# MainSCH.net
KiCad netlist of a schematic drawn in Altium Designer
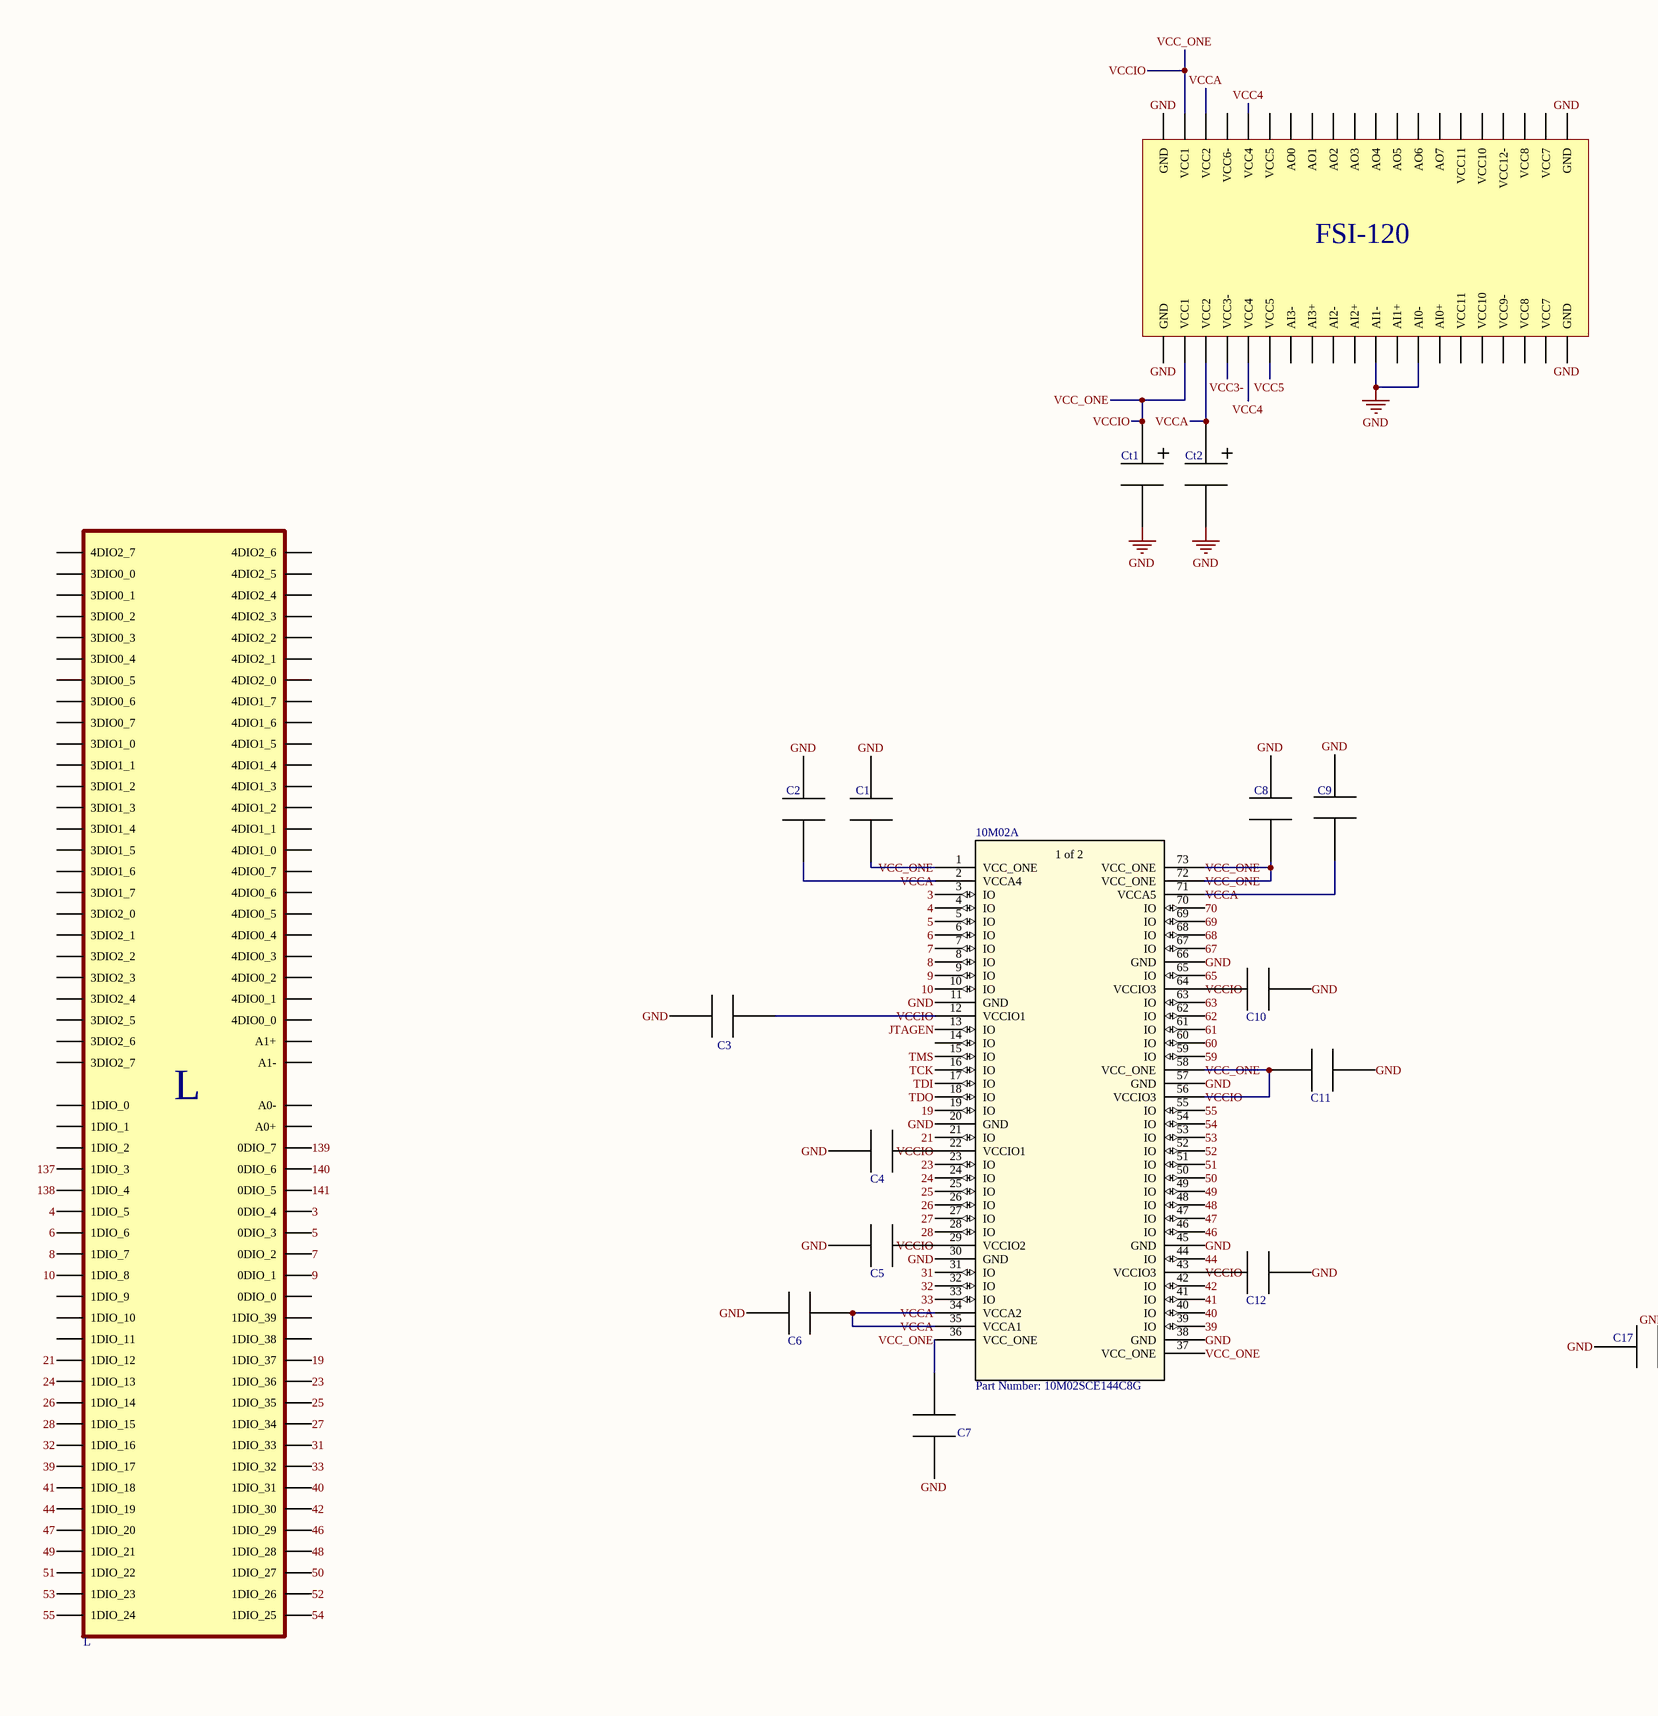
[diagram p0: MainSCH.SchDoc, left]
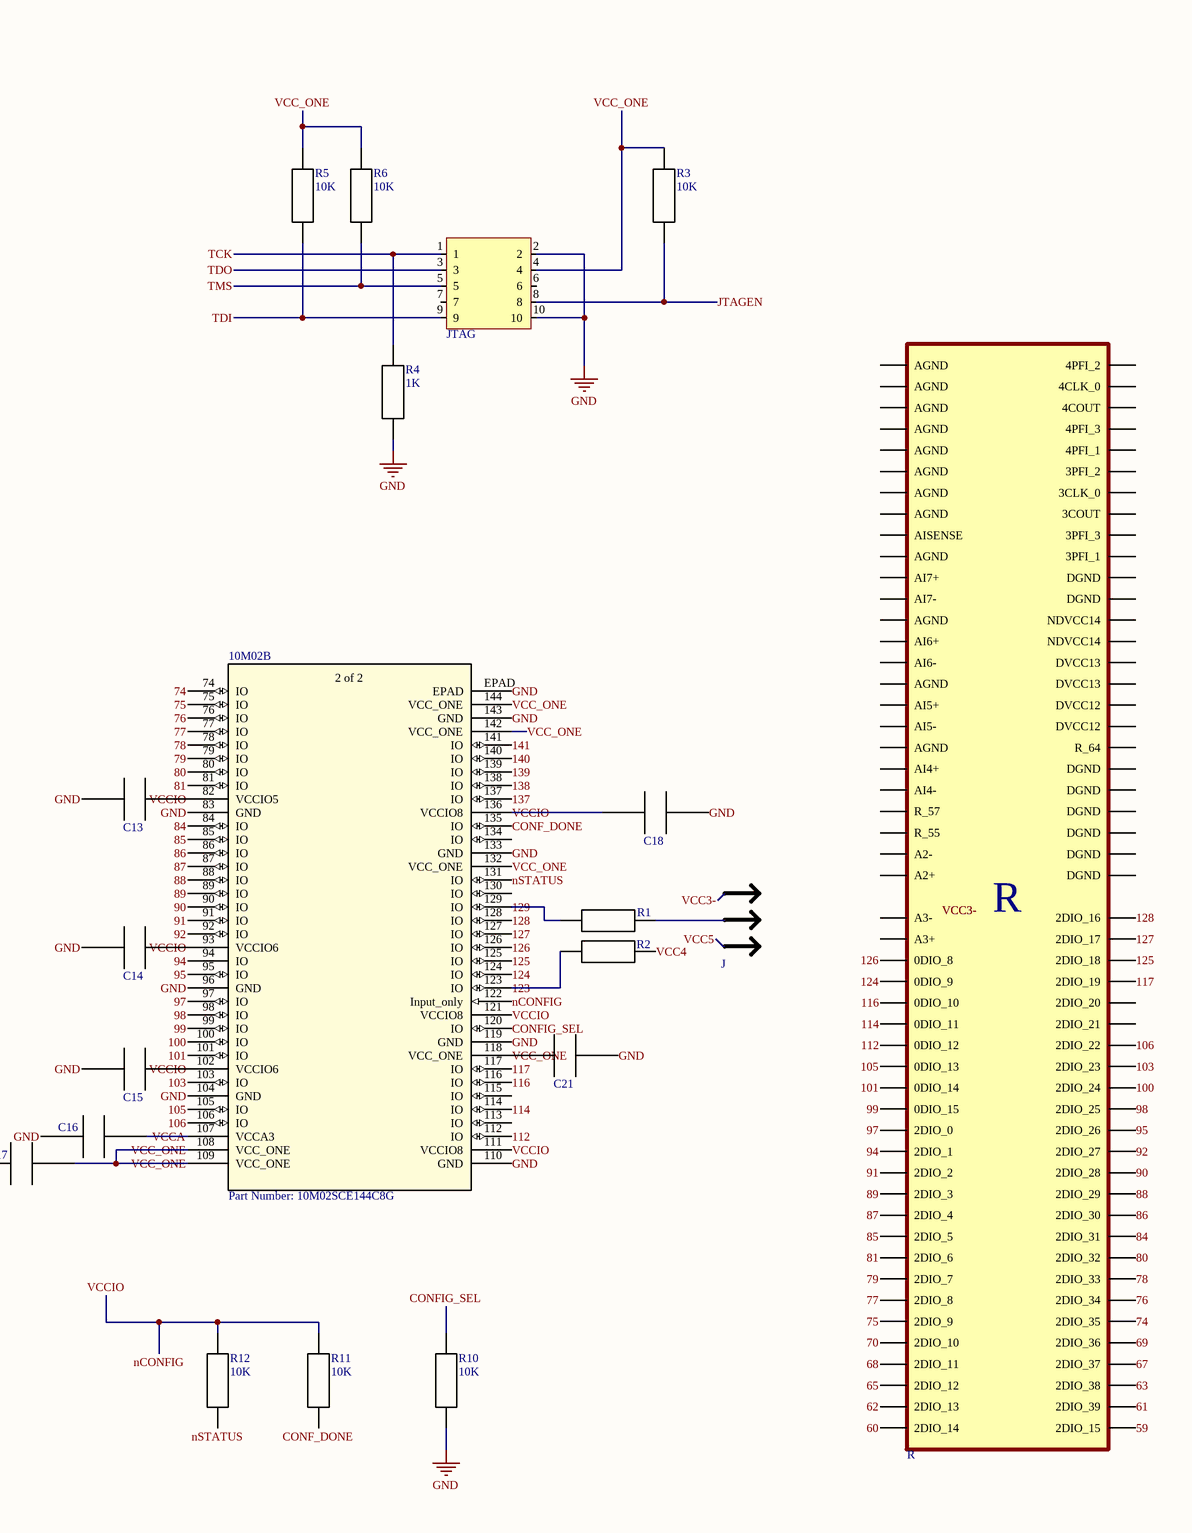
[diagram p1: MainSCH.SchDoc, right]

(export (version "E")
  (design (tool "Eeschema 10.0.6"))
  (components
    (comp (ref "*") (value "JTAG") (footprint "JTAG") (libsource (lib "2020-02-13_08-55-10") (part "JTAG")))
    (comp (ref "10M02")
      (value "Part Number: 10M02SCE144C8G")
      (footprint "EQFP-144_A:1P65_")
      (description "No Description Available")
      (fields
        (field (name "MANUFACTURER_PART_NUMBER") "10M02SCE144C8G")
        (field (name "COPYRIGHT") "Copyright (C) 2018 Accelerated Designs. All rights reserved")
      )
      (libsource (lib "2020-02-13_08-55-10") (part "10M02SCE144C8G"))
    )
    (comp (ref "C1")
      (value "*")
      (footprint "0805")
      (description "0805 ceramic capacitor")
      (libsource (lib "test_lib") (part "C0805"))
    )
    (comp (ref "C2")
      (value "*")
      (footprint "0805")
      (description "0805 ceramic capacitor")
      (libsource (lib "test_lib") (part "C0805"))
    )
    (comp (ref "C3")
      (value "*")
      (footprint "0805")
      (description "0805 ceramic capacitor")
      (libsource (lib "test_lib") (part "C0805"))
    )
    (comp (ref "C4")
      (value "*")
      (footprint "0805")
      (description "0805 ceramic capacitor")
      (libsource (lib "test_lib") (part "C0805"))
    )
    (comp (ref "C5")
      (value "*")
      (footprint "0805")
      (description "0805 ceramic capacitor")
      (libsource (lib "test_lib") (part "C0805"))
    )
    (comp (ref "C6")
      (value "*")
      (footprint "0805")
      (description "0805 ceramic capacitor")
      (libsource (lib "test_lib") (part "C0805"))
    )
    (comp (ref "C7")
      (value "*")
      (footprint "0805")
      (description "0805 ceramic capacitor")
      (libsource (lib "test_lib") (part "C0805"))
    )
    (comp (ref "C8")
      (value "*")
      (footprint "0805")
      (description "0805 ceramic capacitor")
      (libsource (lib "test_lib") (part "C0805"))
    )
    (comp (ref "C9")
      (value "*")
      (footprint "0805")
      (description "0805 ceramic capacitor")
      (libsource (lib "test_lib") (part "C0805"))
    )
    (comp (ref "C10")
      (value "*")
      (footprint "0805")
      (description "0805 ceramic capacitor")
      (libsource (lib "test_lib") (part "C0805"))
    )
    (comp (ref "C11")
      (value "*")
      (footprint "0805")
      (description "0805 ceramic capacitor")
      (libsource (lib "test_lib") (part "C0805"))
    )
    (comp (ref "C12")
      (value "*")
      (footprint "0805")
      (description "0805 ceramic capacitor")
      (libsource (lib "test_lib") (part "C0805"))
    )
    (comp (ref "C13")
      (value "*")
      (footprint "0805")
      (description "0805 ceramic capacitor")
      (libsource (lib "test_lib") (part "C0805"))
    )
    (comp (ref "C14")
      (value "*")
      (footprint "0805")
      (description "0805 ceramic capacitor")
      (libsource (lib "test_lib") (part "C0805"))
    )
    (comp (ref "C15")
      (value "*")
      (footprint "0805")
      (description "0805 ceramic capacitor")
      (libsource (lib "test_lib") (part "C0805"))
    )
    (comp (ref "C16")
      (value "*")
      (footprint "0805")
      (description "0805 ceramic capacitor")
      (libsource (lib "test_lib") (part "C0805"))
    )
    (comp (ref "C17")
      (value "*")
      (footprint "0805")
      (description "0805 ceramic capacitor")
      (libsource (lib "test_lib") (part "C0805"))
    )
    (comp (ref "C18")
      (value "*")
      (footprint "0805")
      (description "0805 ceramic capacitor")
      (libsource (lib "test_lib") (part "C0805"))
    )
    (comp (ref "C21")
      (value "*")
      (footprint "0805")
      (description "0805 ceramic capacitor")
      (libsource (lib "test_lib") (part "C0805"))
    )
    (comp (ref "Ct1")
      (value "C_Ta")
      (footprint "C_Ta")
      (description "tantalum capacitor")
      (libsource (lib "test_lib") (part "C_Ta"))
    )
    (comp (ref "Ct2")
      (value "C_Ta")
      (footprint "C_Ta")
      (description "tantalum capacitor")
      (libsource (lib "test_lib") (part "C_Ta"))
    )
    (comp (ref "J")
      (value "JUMPER_SWITCH_2S")
      (footprint "JUMPER_SWITCH_2S")
      (description "2 state jumper switch")
      (libsource (lib "test_lib") (part "JUMPER_SWITCH_2S"))
    )
    (comp (ref "L")
      (value "FSI-150-L")
      (footprint "FSI-150")
      (description "fsi 150 left")
      (libsource (lib "test_lib") (part "FSI-150-L"))
    )
    (comp (ref "R")
      (value "FSI-150-R")
      (footprint "FSI-150")
      (description "fsi 150 right")
      (libsource (lib "test_lib") (part "FSI-150-R"))
    )
    (comp (ref "R1")
      (value "*")
      (footprint "0805")
      (description "0805 resistor")
      (libsource (lib "test_lib") (part "R0805"))
    )
    (comp (ref "R2")
      (value "*")
      (footprint "0805")
      (description "0805 resistor")
      (libsource (lib "test_lib") (part "R0805"))
    )
    (comp (ref "R3")
      (value "10K")
      (footprint "0805")
      (description "0805 resistor")
      (libsource (lib "test_lib") (part "R0805"))
    )
    (comp (ref "R4")
      (value "1K")
      (footprint "0805")
      (description "0805 resistor")
      (libsource (lib "test_lib") (part "R0805"))
    )
    (comp (ref "R5")
      (value "10K")
      (footprint "0805")
      (description "0805 resistor")
      (libsource (lib "test_lib") (part "R0805"))
    )
    (comp (ref "R6")
      (value "10K")
      (footprint "0805")
      (description "0805 resistor")
      (libsource (lib "test_lib") (part "R0805"))
    )
    (comp (ref "R10")
      (value "10K")
      (footprint "0805")
      (description "0805 resistor")
      (libsource (lib "test_lib") (part "R0805"))
    )
    (comp (ref "R11")
      (value "10K")
      (footprint "0805")
      (description "0805 resistor")
      (libsource (lib "test_lib") (part "R0805"))
    )
    (comp (ref "R12")
      (value "10K")
      (footprint "0805")
      (description "0805 resistor")
      (libsource (lib "test_lib") (part "R0805"))
    )
    (comp (ref "X") (value "FSI120") (footprint "FSI-120") (libsource (lib "test_lib") (part "FSI120")))
  )
  (nets
    (net (code "1") (name "/3") (class "Default")
      (node (ref "10M02") (pin "3") (pinfunction "IO_3") (pintype "bidirectional"))
      (node (ref "L") (pin "R_40") (pinfunction "0DIO_4_R_40") (pintype "passive"))
    )
    (net (code "2") (name "/4") (class "Default")
      (node (ref "10M02") (pin "4") (pinfunction "IO_4") (pintype "bidirectional"))
      (node (ref "L") (pin "R_39") (pinfunction "1DIO_5_R_39") (pintype "passive"))
    )
    (net (code "3") (name "/5") (class "Default")
      (node (ref "10M02") (pin "5") (pinfunction "IO_5") (pintype "bidirectional"))
      (node (ref "L") (pin "R_38") (pinfunction "0DIO_3_R_38") (pintype "passive"))
    )
    (net (code "4") (name "/6") (class "Default")
      (node (ref "10M02") (pin "6") (pinfunction "IO_6") (pintype "bidirectional"))
      (node (ref "L") (pin "R_37") (pinfunction "1DIO_6_R_37") (pintype "passive"))
    )
    (net (code "5") (name "/7") (class "Default")
      (node (ref "10M02") (pin "7") (pinfunction "IO_7") (pintype "bidirectional"))
      (node (ref "L") (pin "R_36") (pinfunction "0DIO_2_R_36") (pintype "passive"))
    )
    (net (code "6") (name "/8") (class "Default")
      (node (ref "10M02") (pin "8") (pinfunction "IO_8") (pintype "bidirectional"))
      (node (ref "L") (pin "R_35") (pinfunction "1DIO_7_R_35") (pintype "passive"))
    )
    (net (code "7") (name "/9") (class "Default")
      (node (ref "10M02") (pin "9") (pinfunction "IO_9") (pintype "bidirectional"))
      (node (ref "L") (pin "R_34") (pinfunction "0DIO_1_R_34") (pintype "passive"))
    )
    (net (code "8") (name "/10") (class "Default")
      (node (ref "10M02") (pin "10") (pinfunction "IO_10") (pintype "bidirectional"))
      (node (ref "L") (pin "R_33") (pinfunction "1DIO_8_R_33") (pintype "passive"))
    )
    (net (code "9") (name "/19") (class "Default")
      (node (ref "10M02") (pin "19") (pinfunction "IO_19") (pintype "bidirectional"))
      (node (ref "L") (pin "R_26") (pinfunction "1DIO_37_R_26") (pintype "passive"))
    )
    (net (code "10") (name "/21") (class "Default")
      (node (ref "10M02") (pin "21") (pinfunction "IO_21") (pintype "bidirectional"))
      (node (ref "L") (pin "R_25") (pinfunction "1DIO_12_R_25") (pintype "passive"))
    )
    (net (code "11") (name "/23") (class "Default")
      (node (ref "10M02") (pin "23") (pinfunction "IO_23") (pintype "bidirectional"))
      (node (ref "L") (pin "R_24") (pinfunction "1DIO_36_R_24") (pintype "passive"))
    )
    (net (code "12") (name "/24") (class "Default")
      (node (ref "10M02") (pin "24") (pinfunction "IO_24") (pintype "bidirectional"))
      (node (ref "L") (pin "R_23") (pinfunction "1DIO_13_R_23") (pintype "passive"))
    )
    (net (code "13") (name "/25") (class "Default")
      (node (ref "10M02") (pin "25") (pinfunction "IO_25") (pintype "bidirectional"))
      (node (ref "L") (pin "R_22") (pinfunction "1DIO_35_R_22") (pintype "passive"))
    )
    (net (code "14") (name "/26") (class "Default")
      (node (ref "10M02") (pin "26") (pinfunction "IO_26") (pintype "bidirectional"))
      (node (ref "L") (pin "R_21") (pinfunction "1DIO_14_R_21") (pintype "passive"))
    )
    (net (code "15") (name "/27") (class "Default")
      (node (ref "10M02") (pin "27") (pinfunction "IO_27") (pintype "bidirectional"))
      (node (ref "L") (pin "R_20") (pinfunction "1DIO_34_R_20") (pintype "passive"))
    )
    (net (code "16") (name "/28") (class "Default")
      (node (ref "10M02") (pin "28") (pinfunction "IO_28") (pintype "bidirectional"))
      (node (ref "L") (pin "R_19") (pinfunction "1DIO_15_R_19") (pintype "passive"))
    )
    (net (code "17") (name "/31") (class "Default")
      (node (ref "10M02") (pin "31") (pinfunction "IO_31") (pintype "bidirectional"))
      (node (ref "L") (pin "R_18") (pinfunction "1DIO_33_R_18") (pintype "passive"))
    )
    (net (code "18") (name "/32") (class "Default")
      (node (ref "10M02") (pin "32") (pinfunction "IO_32") (pintype "bidirectional"))
      (node (ref "L") (pin "R_17") (pinfunction "1DIO_16_R_17") (pintype "passive"))
    )
    (net (code "19") (name "/33") (class "Default")
      (node (ref "10M02") (pin "33") (pinfunction "IO_33") (pintype "bidirectional"))
      (node (ref "L") (pin "R_16") (pinfunction "1DIO_32_R_16") (pintype "passive"))
    )
    (net (code "20") (name "/39") (class "Default")
      (node (ref "10M02") (pin "39") (pinfunction "IO_39") (pintype "bidirectional"))
      (node (ref "L") (pin "R_15") (pinfunction "1DIO_17_R_15") (pintype "passive"))
    )
    (net (code "21") (name "/40") (class "Default")
      (node (ref "10M02") (pin "40") (pinfunction "IO_40") (pintype "bidirectional"))
      (node (ref "L") (pin "R_14") (pinfunction "1DIO_31_R_14") (pintype "passive"))
    )
    (net (code "22") (name "/41") (class "Default")
      (node (ref "10M02") (pin "41") (pinfunction "IO_41") (pintype "bidirectional"))
      (node (ref "L") (pin "R_13") (pinfunction "1DIO_18_R_13") (pintype "passive"))
    )
    (net (code "23") (name "/42") (class "Default")
      (node (ref "10M02") (pin "42") (pinfunction "IO_42") (pintype "bidirectional"))
      (node (ref "L") (pin "R_12") (pinfunction "1DIO_30_R_12") (pintype "passive"))
    )
    (net (code "24") (name "/44") (class "Default")
      (node (ref "10M02") (pin "44") (pinfunction "IO_44") (pintype "bidirectional"))
      (node (ref "L") (pin "R_11") (pinfunction "1DIO_19_R_11") (pintype "passive"))
    )
    (net (code "25") (name "/46") (class "Default")
      (node (ref "10M02") (pin "46") (pinfunction "IO_46") (pintype "bidirectional"))
      (node (ref "L") (pin "R_10") (pinfunction "1DIO_29_R_10") (pintype "passive"))
    )
    (net (code "26") (name "/47") (class "Default")
      (node (ref "10M02") (pin "47") (pinfunction "IO_47") (pintype "bidirectional"))
      (node (ref "L") (pin "R_9") (pinfunction "1DIO_20_R_9") (pintype "passive"))
    )
    (net (code "27") (name "/48") (class "Default")
      (node (ref "10M02") (pin "48") (pinfunction "IO_48") (pintype "bidirectional"))
      (node (ref "L") (pin "R_8") (pinfunction "1DIO_28_R_8") (pintype "passive"))
    )
    (net (code "28") (name "/49") (class "Default")
      (node (ref "10M02") (pin "49") (pinfunction "IO_49") (pintype "bidirectional"))
      (node (ref "L") (pin "R_7") (pinfunction "1DIO_21_R_7") (pintype "passive"))
    )
    (net (code "29") (name "/50") (class "Default")
      (node (ref "10M02") (pin "50") (pinfunction "IO_50") (pintype "bidirectional"))
      (node (ref "L") (pin "R_6") (pinfunction "1DIO_27_R_6") (pintype "passive"))
    )
    (net (code "30") (name "/51") (class "Default")
      (node (ref "10M02") (pin "51") (pinfunction "IO_51") (pintype "bidirectional"))
      (node (ref "L") (pin "R_5") (pinfunction "1DIO_22_R_5") (pintype "passive"))
    )
    (net (code "31") (name "/52") (class "Default")
      (node (ref "10M02") (pin "52") (pinfunction "IO_52") (pintype "bidirectional"))
      (node (ref "L") (pin "R_4") (pinfunction "1DIO_26_R_4") (pintype "passive"))
    )
    (net (code "32") (name "/53") (class "Default")
      (node (ref "10M02") (pin "53") (pinfunction "IO_53") (pintype "bidirectional"))
      (node (ref "L") (pin "R_3") (pinfunction "1DIO_23_R_3") (pintype "passive"))
    )
    (net (code "33") (name "/54") (class "Default")
      (node (ref "10M02") (pin "54") (pinfunction "IO_54") (pintype "bidirectional"))
      (node (ref "L") (pin "R_2") (pinfunction "1DIO_25_R_2") (pintype "passive"))
    )
    (net (code "34") (name "/55") (class "Default")
      (node (ref "10M02") (pin "55") (pinfunction "IO_55") (pintype "bidirectional"))
      (node (ref "L") (pin "R_1") (pinfunction "1DIO_24_R_1") (pintype "passive"))
    )
    (net (code "35") (name "/59") (class "Default")
      (node (ref "10M02") (pin "59") (pinfunction "IO_59") (pintype "bidirectional"))
      (node (ref "R") (pin "R_2") (pinfunction "2DIO_15_R_2") (pintype "passive"))
    )
    (net (code "36") (name "/60") (class "Default")
      (node (ref "10M02") (pin "60") (pinfunction "IO_60") (pintype "bidirectional"))
      (node (ref "R") (pin "R_1") (pinfunction "2DIO_14_R_1") (pintype "passive"))
    )
    (net (code "37") (name "/61") (class "Default")
      (node (ref "10M02") (pin "61") (pinfunction "IO_61") (pintype "bidirectional"))
      (node (ref "R") (pin "R_4") (pinfunction "2DIO_39_R_4") (pintype "passive"))
    )
    (net (code "38") (name "/62") (class "Default")
      (node (ref "10M02") (pin "62") (pinfunction "IO_62") (pintype "bidirectional"))
      (node (ref "R") (pin "R_3") (pinfunction "2DIO_13_R_3") (pintype "passive"))
    )
    (net (code "39") (name "/63") (class "Default")
      (node (ref "10M02") (pin "63") (pinfunction "IO_63") (pintype "bidirectional"))
      (node (ref "R") (pin "R_6") (pinfunction "2DIO_38_R_6") (pintype "passive"))
    )
    (net (code "40") (name "/65") (class "Default")
      (node (ref "10M02") (pin "65") (pinfunction "IO_65") (pintype "bidirectional"))
      (node (ref "R") (pin "R_5") (pinfunction "2DIO_12_R_5") (pintype "passive"))
    )
    (net (code "41") (name "/67") (class "Default")
      (node (ref "10M02") (pin "67") (pinfunction "IO_67") (pintype "bidirectional"))
      (node (ref "R") (pin "R_8") (pinfunction "2DIO_37_R_8") (pintype "passive"))
    )
    (net (code "42") (name "/68") (class "Default")
      (node (ref "10M02") (pin "68") (pinfunction "IO_68") (pintype "bidirectional"))
      (node (ref "R") (pin "R_7") (pinfunction "2DIO_11_R_7") (pintype "passive"))
    )
    (net (code "43") (name "/69") (class "Default")
      (node (ref "10M02") (pin "69") (pinfunction "IO_69") (pintype "bidirectional"))
      (node (ref "R") (pin "R_10") (pinfunction "2DIO_36_R_10") (pintype "passive"))
    )
    (net (code "44") (name "/70") (class "Default")
      (node (ref "10M02") (pin "70") (pinfunction "IO_70") (pintype "bidirectional"))
      (node (ref "R") (pin "R_9") (pinfunction "2DIO_10_R_9") (pintype "passive"))
    )
    (net (code "45") (name "/74") (class "Default")
      (node (ref "10M02") (pin "74") (pinfunction "IO_74") (pintype "bidirectional"))
      (node (ref "R") (pin "R_12") (pinfunction "2DIO_35_R_12") (pintype "passive"))
    )
    (net (code "46") (name "/75") (class "Default")
      (node (ref "10M02") (pin "75") (pinfunction "IO_75") (pintype "bidirectional"))
      (node (ref "R") (pin "R_11") (pinfunction "2DIO_9_R_11") (pintype "passive"))
    )
    (net (code "47") (name "/76") (class "Default")
      (node (ref "10M02") (pin "76") (pinfunction "IO_76") (pintype "bidirectional"))
      (node (ref "R") (pin "R_14") (pinfunction "2DIO_34_R_14") (pintype "passive"))
    )
    (net (code "48") (name "/77") (class "Default")
      (node (ref "10M02") (pin "77") (pinfunction "IO_77") (pintype "bidirectional"))
      (node (ref "R") (pin "R_13") (pinfunction "2DIO_8_R_13") (pintype "passive"))
    )
    (net (code "49") (name "/78") (class "Default")
      (node (ref "10M02") (pin "78") (pinfunction "IO_78") (pintype "bidirectional"))
      (node (ref "R") (pin "R_16") (pinfunction "2DIO_33_R_16") (pintype "passive"))
    )
    (net (code "50") (name "/79") (class "Default")
      (node (ref "10M02") (pin "79") (pinfunction "IO_79") (pintype "bidirectional"))
      (node (ref "R") (pin "R_15") (pinfunction "2DIO_7_R_15") (pintype "passive"))
    )
    (net (code "51") (name "/80") (class "Default")
      (node (ref "10M02") (pin "80") (pinfunction "IO_80") (pintype "bidirectional"))
      (node (ref "R") (pin "R_18") (pinfunction "2DIO_32_R_18") (pintype "passive"))
    )
    (net (code "52") (name "/81") (class "Default")
      (node (ref "10M02") (pin "81") (pinfunction "IO_81") (pintype "bidirectional"))
      (node (ref "R") (pin "R_17") (pinfunction "2DIO_6_R_17") (pintype "passive"))
    )
    (net (code "53") (name "/84") (class "Default")
      (node (ref "10M02") (pin "84") (pinfunction "IO_84") (pintype "bidirectional"))
      (node (ref "R") (pin "R_20") (pinfunction "2DIO_31_R_20") (pintype "passive"))
    )
    (net (code "54") (name "/85") (class "Default")
      (node (ref "10M02") (pin "85") (pinfunction "IO_85") (pintype "bidirectional"))
      (node (ref "R") (pin "R_19") (pinfunction "2DIO_5_R_19") (pintype "passive"))
    )
    (net (code "55") (name "/86") (class "Default")
      (node (ref "10M02") (pin "86") (pinfunction "IO_86") (pintype "bidirectional"))
      (node (ref "R") (pin "R_22") (pinfunction "2DIO_30_R_22") (pintype "passive"))
    )
    (net (code "56") (name "/87") (class "Default")
      (node (ref "10M02") (pin "87") (pinfunction "IO_87") (pintype "bidirectional"))
      (node (ref "R") (pin "R_21") (pinfunction "2DIO_4_R_21") (pintype "passive"))
    )
    (net (code "57") (name "/88") (class "Default")
      (node (ref "10M02") (pin "88") (pinfunction "IO_88") (pintype "bidirectional"))
      (node (ref "R") (pin "R_24") (pinfunction "2DIO_29_R_24") (pintype "passive"))
    )
    (net (code "58") (name "/89") (class "Default")
      (node (ref "10M02") (pin "89") (pinfunction "IO_89") (pintype "bidirectional"))
      (node (ref "R") (pin "R_23") (pinfunction "2DIO_3_R_23") (pintype "passive"))
    )
    (net (code "59") (name "/90") (class "Default")
      (node (ref "10M02") (pin "90") (pinfunction "IO_90") (pintype "bidirectional"))
      (node (ref "R") (pin "R_26") (pinfunction "2DIO_28_R_26") (pintype "passive"))
    )
    (net (code "60") (name "/91") (class "Default")
      (node (ref "10M02") (pin "91") (pinfunction "IO_91") (pintype "bidirectional"))
      (node (ref "R") (pin "R_25") (pinfunction "2DIO_2_R_25") (pintype "passive"))
    )
    (net (code "61") (name "/92") (class "Default")
      (node (ref "10M02") (pin "92") (pinfunction "IO_92") (pintype "bidirectional"))
      (node (ref "R") (pin "R_28") (pinfunction "2DIO_27_R_28") (pintype "passive"))
    )
    (net (code "62") (name "/94") (class "Default")
      (node (ref "10M02") (pin "94") (pinfunction "IO_94") (pintype "power_in"))
      (node (ref "R") (pin "R_27") (pinfunction "2DIO_1_R_27") (pintype "passive"))
    )
    (net (code "63") (name "/95") (class "Default")
      (node (ref "10M02") (pin "95") (pinfunction "IO_95") (pintype "bidirectional"))
      (node (ref "R") (pin "R_30") (pinfunction "2DIO_26_R_30") (pintype "passive"))
    )
    (net (code "64") (name "/97") (class "Default")
      (node (ref "10M02") (pin "97") (pinfunction "IO_97") (pintype "bidirectional"))
      (node (ref "R") (pin "R_29") (pinfunction "2DIO_0_R_29") (pintype "passive"))
    )
    (net (code "65") (name "/98") (class "Default")
      (node (ref "10M02") (pin "98") (pinfunction "IO_98") (pintype "bidirectional"))
      (node (ref "R") (pin "R_32") (pinfunction "2DIO_25_R_32") (pintype "passive"))
    )
    (net (code "66") (name "/99") (class "Default")
      (node (ref "10M02") (pin "99") (pinfunction "IO_99") (pintype "bidirectional"))
      (node (ref "R") (pin "R_31") (pinfunction "0DIO_15_R_31") (pintype "passive"))
    )
    (net (code "67") (name "/100") (class "Default")
      (node (ref "10M02") (pin "100") (pinfunction "IO_100") (pintype "bidirectional"))
      (node (ref "R") (pin "R_34") (pinfunction "2DIO_24_R_34") (pintype "passive"))
    )
    (net (code "68") (name "/101") (class "Default")
      (node (ref "10M02") (pin "101") (pinfunction "IO_101") (pintype "bidirectional"))
      (node (ref "R") (pin "R_33") (pinfunction "0DIO_14_R_33") (pintype "passive"))
    )
    (net (code "69") (name "/103") (class "Default")
      (node (ref "10M02") (pin "103") (pinfunction "IO_103") (pintype "bidirectional"))
      (node (ref "R") (pin "R_36") (pinfunction "2DIO_23_R_36") (pintype "passive"))
    )
    (net (code "70") (name "/105") (class "Default")
      (node (ref "10M02") (pin "105") (pinfunction "IO_105") (pintype "bidirectional"))
      (node (ref "R") (pin "R_35") (pinfunction "0DIO_13_R_35") (pintype "passive"))
    )
    (net (code "71") (name "/106") (class "Default")
      (node (ref "10M02") (pin "106") (pinfunction "IO_106") (pintype "bidirectional"))
      (node (ref "R") (pin "R_38") (pinfunction "2DIO_22_R_38") (pintype "passive"))
    )
    (net (code "72") (name "/112") (class "Default")
      (node (ref "10M02") (pin "112") (pinfunction "IO_112") (pintype "bidirectional"))
      (node (ref "R") (pin "R_37") (pinfunction "0DIO_12_R_37") (pintype "passive"))
    )
    (net (code "73") (name "/114") (class "Default")
      (node (ref "10M02") (pin "114") (pinfunction "IO_114") (pintype "bidirectional"))
      (node (ref "R") (pin "R_39") (pinfunction "0DIO_11_R_39") (pintype "passive"))
    )
    (net (code "74") (name "/116") (class "Default")
      (node (ref "10M02") (pin "116") (pinfunction "IO_116") (pintype "bidirectional"))
      (node (ref "R") (pin "R_41") (pinfunction "0DIO_10_R_41") (pintype "passive"))
    )
    (net (code "75") (name "/117") (class "Default")
      (node (ref "10M02") (pin "117") (pinfunction "IO_117") (pintype "bidirectional"))
      (node (ref "R") (pin "R_44") (pinfunction "2DIO_19_R_44") (pintype "passive"))
    )
    (net (code "76") (name "/123") (class "Default")
      (node (ref "10M02") (pin "123") (pinfunction "IO_123") (pintype "bidirectional"))
      (node (ref "R2") (pin "1") (pinfunction "1_1") (pintype "passive"))
    )
    (net (code "77") (name "/124") (class "Default")
      (node (ref "10M02") (pin "124") (pinfunction "IO_124") (pintype "bidirectional"))
      (node (ref "R") (pin "R_43") (pinfunction "0DIO_9_R_43") (pintype "passive"))
    )
    (net (code "78") (name "/125") (class "Default")
      (node (ref "10M02") (pin "125") (pinfunction "IO_125") (pintype "bidirectional"))
      (node (ref "R") (pin "R_46") (pinfunction "2DIO_18_R_46") (pintype "passive"))
    )
    (net (code "79") (name "/126") (class "Default")
      (node (ref "10M02") (pin "126") (pinfunction "IO_126") (pintype "bidirectional"))
      (node (ref "R") (pin "R_45") (pinfunction "0DIO_8_R_45") (pintype "passive"))
    )
    (net (code "80") (name "/127") (class "Default")
      (node (ref "10M02") (pin "127") (pinfunction "IO_127") (pintype "bidirectional"))
      (node (ref "R") (pin "R_48") (pinfunction "2DIO_17_R_48") (pintype "passive"))
    )
    (net (code "81") (name "/128") (class "Default")
      (node (ref "10M02") (pin "128") (pinfunction "IO_128") (pintype "bidirectional"))
      (node (ref "R") (pin "R_50") (pinfunction "2DIO_16_R_50") (pintype "passive"))
    )
    (net (code "82") (name "/129") (class "Default")
      (node (ref "10M02") (pin "129") (pinfunction "IO_129") (pintype "bidirectional"))
      (node (ref "R1") (pin "1") (pinfunction "1_1") (pintype "passive"))
    )
    (net (code "83") (name "/137") (class "Default")
      (node (ref "10M02") (pin "137") (pinfunction "IO_137") (pintype "bidirectional"))
      (node (ref "L") (pin "R_43") (pinfunction "1DIO_3_R_43") (pintype "passive"))
    )
    (net (code "84") (name "/138") (class "Default")
      (node (ref "10M02") (pin "138") (pinfunction "IO_138") (pintype "bidirectional"))
      (node (ref "L") (pin "R_41") (pinfunction "1DIO_4_R_41") (pintype "passive"))
    )
    (net (code "85") (name "/139") (class "Default")
      (node (ref "10M02") (pin "139") (pinfunction "IO_139") (pintype "bidirectional"))
      (node (ref "L") (pin "R_46") (pinfunction "0DIO_7_R_46") (pintype "passive"))
    )
    (net (code "86") (name "/140") (class "Default")
      (node (ref "10M02") (pin "140") (pinfunction "IO_140") (pintype "bidirectional"))
      (node (ref "L") (pin "R_44") (pinfunction "0DIO_6_R_44") (pintype "passive"))
    )
    (net (code "87") (name "/141") (class "Default")
      (node (ref "10M02") (pin "141") (pinfunction "IO_141") (pintype "bidirectional"))
      (node (ref "L") (pin "R_42") (pinfunction "0DIO_5_R_42") (pintype "passive"))
    )
    (net (code "88") (name "/CONFIG_SEL") (class "Default")
      (node (ref "10M02") (pin "120") (pinfunction "IO_120") (pintype "bidirectional"))
      (node (ref "R10") (pin "2") (pinfunction "2_2") (pintype "passive"))
    )
    (net (code "89") (name "/CONF_DONE") (class "Default")
      (node (ref "10M02") (pin "135") (pinfunction "IO_135") (pintype "bidirectional"))
      (node (ref "R11") (pin "1") (pinfunction "1_1") (pintype "passive"))
    )
    (net (code "90") (name "/JTAGEN") (class "Default")
      (node (ref "*") (pin "8") (pinfunction "8_8") (pintype "passive"))
      (node (ref "10M02") (pin "13") (pinfunction "IO_13") (pintype "bidirectional"))
      (node (ref "R3") (pin "1") (pinfunction "1_1") (pintype "passive"))
    )
    (net (code "91") (name "/TCK") (class "Default")
      (node (ref "*") (pin "1") (pinfunction "1_1") (pintype "passive"))
      (node (ref "10M02") (pin "16") (pinfunction "IO_16") (pintype "bidirectional"))
      (node (ref "R4") (pin "2") (pinfunction "2_2") (pintype "passive"))
    )
    (net (code "92") (name "/TDI") (class "Default")
      (node (ref "*") (pin "9") (pinfunction "9_9") (pintype "passive"))
      (node (ref "10M02") (pin "17") (pinfunction "IO_17") (pintype "bidirectional"))
      (node (ref "R5") (pin "1") (pinfunction "1_1") (pintype "passive"))
    )
    (net (code "93") (name "/TDO") (class "Default")
      (node (ref "*") (pin "3") (pinfunction "3_3") (pintype "passive"))
      (node (ref "10M02") (pin "18") (pinfunction "IO_18") (pintype "bidirectional"))
    )
    (net (code "94") (name "/TMS") (class "Default")
      (node (ref "*") (pin "5") (pinfunction "5_5") (pintype "passive"))
      (node (ref "10M02") (pin "15") (pinfunction "IO_15") (pintype "bidirectional"))
      (node (ref "R6") (pin "1") (pinfunction "1_1") (pintype "passive"))
    )
    (net (code "95") (name "/VCC3-") (class "Default")
      (node (ref "J") (pin "1") (pinfunction "1_1") (pintype "passive"))
      (node (ref "X") (pin "17") (pinfunction "VCC3-_17") (pintype "passive"))
    )
    (net (code "96") (name "/VCC4") (class "Default")
      (node (ref "R2") (pin "2") (pinfunction "2_2") (pintype "passive"))
      (node (ref "X") (pin "16") (pinfunction "VCC4_16") (pintype "passive"))
      (node (ref "X") (pin "25") (pinfunction "VCC4_25") (pintype "passive"))
    )
    (net (code "97") (name "/VCC5") (class "Default")
      (node (ref "J") (pin "2") (pinfunction "2_2") (pintype "passive"))
      (node (ref "X") (pin "15") (pinfunction "VCC5_15") (pintype "passive"))
    )
    (net (code "98") (name "/VCCA") (class "Default")
      (node (ref "10M02") (pin "107") (pinfunction "VCCA3_107") (pintype "power_in"))
      (node (ref "10M02") (pin "2") (pinfunction "VCCA4_2") (pintype "power_in"))
      (node (ref "10M02") (pin "34") (pinfunction "VCCA2_34") (pintype "power_in"))
      (node (ref "10M02") (pin "35") (pinfunction "VCCA1_35") (pintype "power_in"))
      (node (ref "10M02") (pin "71") (pinfunction "VCCA5_71") (pintype "power_in"))
      (node (ref "C16") (pin "1") (pinfunction "1_1") (pintype "passive"))
      (node (ref "C2") (pin "1") (pinfunction "1_1") (pintype "passive"))
      (node (ref "C6") (pin "2") (pinfunction "2_2") (pintype "passive"))
      (node (ref "C9") (pin "1") (pinfunction "1_1") (pintype "passive"))
      (node (ref "Ct2") (pin "1") (pinfunction "1_1") (pintype "passive"))
      (node (ref "X") (pin "18") (pinfunction "VCC2_18") (pintype "passive"))
      (node (ref "X") (pin "23") (pinfunction "VCC2_23") (pintype "passive"))
    )
    (net (code "99") (name "/VCCIO") (class "Default")
      (node (ref "*") (pin "4") (pinfunction "4_4") (pintype "passive"))
      (node (ref "10M02") (pin "1") (pinfunction "VCC_ONE_1") (pintype "power_in"))
      (node (ref "10M02") (pin "102") (pinfunction "VCCIO6_102") (pintype "power_in"))
      (node (ref "10M02") (pin "108") (pinfunction "VCC_ONE_108") (pintype "power_in"))
      (node (ref "10M02") (pin "109") (pinfunction "VCC_ONE_109") (pintype "power_in"))
      (node (ref "10M02") (pin "111") (pinfunction "VCCIO8_111") (pintype "power_in"))
      (node (ref "10M02") (pin "118") (pinfunction "VCC_ONE_118") (pintype "power_in"))
      (node (ref "10M02") (pin "12") (pinfunction "VCCIO1_12") (pintype "power_in"))
      (node (ref "10M02") (pin "121") (pinfunction "VCCIO8_121") (pintype "power_in"))
      (node (ref "10M02") (pin "122") (pinfunction "Input_only_122") (pintype "input"))
      (node (ref "10M02") (pin "132") (pinfunction "VCC_ONE_132") (pintype "power_in"))
      (node (ref "10M02") (pin "136") (pinfunction "VCCIO8_136") (pintype "power_in"))
      (node (ref "10M02") (pin "142") (pinfunction "VCC_ONE_142") (pintype "power_in"))
      (node (ref "10M02") (pin "144") (pinfunction "VCC_ONE_144") (pintype "power_in"))
      (node (ref "10M02") (pin "22") (pinfunction "VCCIO1_22") (pintype "power_in"))
      (node (ref "10M02") (pin "29") (pinfunction "VCCIO2_29") (pintype "power_in"))
      (node (ref "10M02") (pin "36") (pinfunction "VCC_ONE_36") (pintype "power_in"))
      (node (ref "10M02") (pin "37") (pinfunction "VCC_ONE_37") (pintype "power_in"))
      (node (ref "10M02") (pin "43") (pinfunction "VCCIO3_43") (pintype "power_in"))
      (node (ref "10M02") (pin "56") (pinfunction "VCCIO3_56") (pintype "power_in"))
      (node (ref "10M02") (pin "58") (pinfunction "VCC_ONE_58") (pintype "power_in"))
      (node (ref "10M02") (pin "64") (pinfunction "VCCIO3_64") (pintype "power_in"))
      (node (ref "10M02") (pin "72") (pinfunction "VCC_ONE_72") (pintype "power_in"))
      (node (ref "10M02") (pin "73") (pinfunction "VCC_ONE_73") (pintype "power_in"))
      (node (ref "10M02") (pin "82") (pinfunction "VCCIO5_82") (pintype "power_in"))
      (node (ref "10M02") (pin "93") (pinfunction "VCCIO6_93") (pintype "power_in"))
      (node (ref "C1") (pin "1") (pinfunction "1_1") (pintype "passive"))
      (node (ref "C10") (pin "1") (pinfunction "1_1") (pintype "passive"))
      (node (ref "C11") (pin "1") (pinfunction "1_1") (pintype "passive"))
      (node (ref "C12") (pin "1") (pinfunction "1_1") (pintype "passive"))
      (node (ref "C13") (pin "2") (pinfunction "2_2") (pintype "passive"))
      (node (ref "C14") (pin "2") (pinfunction "2_2") (pintype "passive"))
      (node (ref "C15") (pin "1") (pinfunction "1_1") (pintype "passive"))
      (node (ref "C17") (pin "1") (pinfunction "1_1") (pintype "passive"))
      (node (ref "C18") (pin "1") (pinfunction "1_1") (pintype "passive"))
      (node (ref "C21") (pin "1") (pinfunction "1_1") (pintype "passive"))
      (node (ref "C3") (pin "1") (pinfunction "1_1") (pintype "passive"))
      (node (ref "C4") (pin "1") (pinfunction "1_1") (pintype "passive"))
      (node (ref "C5") (pin "1") (pinfunction "1_1") (pintype "passive"))
      (node (ref "C7") (pin "2") (pinfunction "2_2") (pintype "passive"))
      (node (ref "C8") (pin "1") (pinfunction "1_1") (pintype "passive"))
      (node (ref "Ct1") (pin "1") (pinfunction "1_1") (pintype "passive"))
      (node (ref "R11") (pin "2") (pinfunction "2_2") (pintype "passive"))
      (node (ref "R12") (pin "2") (pinfunction "2_2") (pintype "passive"))
      (node (ref "R3") (pin "2") (pinfunction "2_2") (pintype "passive"))
      (node (ref "R5") (pin "2") (pinfunction "2_2") (pintype "passive"))
      (node (ref "R6") (pin "2") (pinfunction "2_2") (pintype "passive"))
      (node (ref "X") (pin "19") (pinfunction "VCC1_19") (pintype "passive"))
      (node (ref "X") (pin "22") (pinfunction "VCC1_22") (pintype "passive"))
    )
    (net (code "100") (name "/nSTATUS") (class "Default")
      (node (ref "10M02") (pin "131") (pinfunction "IO_131") (pintype "bidirectional"))
      (node (ref "R12") (pin "1") (pinfunction "1_1") (pintype "passive"))
    )
    (net (code "101") (name "GND") (class "Default")
      (node (ref "*") (pin "10") (pinfunction "10_10") (pintype "passive"))
      (node (ref "*") (pin "2") (pinfunction "2_2") (pintype "passive"))
      (node (ref "10M02") (pin "104") (pinfunction "GND_104") (pintype "passive"))
      (node (ref "10M02") (pin "11") (pinfunction "GND_11") (pintype "passive"))
      (node (ref "10M02") (pin "110") (pinfunction "GND_110") (pintype "passive"))
      (node (ref "10M02") (pin "119") (pinfunction "GND_119") (pintype "passive"))
      (node (ref "10M02") (pin "133") (pinfunction "GND_133") (pintype "passive"))
      (node (ref "10M02") (pin "143") (pinfunction "GND_143") (pintype "passive"))
      (node (ref "10M02") (pin "20") (pinfunction "GND_20") (pintype "passive"))
      (node (ref "10M02") (pin "30") (pinfunction "GND_30") (pintype "passive"))
      (node (ref "10M02") (pin "38") (pinfunction "GND_38") (pintype "passive"))
      (node (ref "10M02") (pin "45") (pinfunction "GND_45") (pintype "passive"))
      (node (ref "10M02") (pin "57") (pinfunction "GND_57") (pintype "passive"))
      (node (ref "10M02") (pin "66") (pinfunction "GND_66") (pintype "passive"))
      (node (ref "10M02") (pin "83") (pinfunction "GND_83") (pintype "passive"))
      (node (ref "10M02") (pin "96") (pinfunction "GND_96") (pintype "passive"))
      (node (ref "10M02") (pin "EPAD") (pinfunction "EPAD_EPAD") (pintype "passive"))
      (node (ref "C1") (pin "2") (pinfunction "2_2") (pintype "passive"))
      (node (ref "C10") (pin "2") (pinfunction "2_2") (pintype "passive"))
      (node (ref "C11") (pin "2") (pinfunction "2_2") (pintype "passive"))
      (node (ref "C12") (pin "2") (pinfunction "2_2") (pintype "passive"))
      (node (ref "C13") (pin "1") (pinfunction "1_1") (pintype "passive"))
      (node (ref "C14") (pin "1") (pinfunction "1_1") (pintype "passive"))
      (node (ref "C15") (pin "2") (pinfunction "2_2") (pintype "passive"))
      (node (ref "C16") (pin "2") (pinfunction "2_2") (pintype "passive"))
      (node (ref "C17") (pin "2") (pinfunction "2_2") (pintype "passive"))
      (node (ref "C18") (pin "2") (pinfunction "2_2") (pintype "passive"))
      (node (ref "C2") (pin "2") (pinfunction "2_2") (pintype "passive"))
      (node (ref "C21") (pin "2") (pinfunction "2_2") (pintype "passive"))
      (node (ref "C3") (pin "2") (pinfunction "2_2") (pintype "passive"))
      (node (ref "C4") (pin "2") (pinfunction "2_2") (pintype "passive"))
      (node (ref "C5") (pin "2") (pinfunction "2_2") (pintype "passive"))
      (node (ref "C6") (pin "1") (pinfunction "1_1") (pintype "passive"))
      (node (ref "C7") (pin "1") (pinfunction "1_1") (pintype "passive"))
      (node (ref "C8") (pin "2") (pinfunction "2_2") (pintype "passive"))
      (node (ref "C9") (pin "2") (pinfunction "2_2") (pintype "passive"))
      (node (ref "Ct1") (pin "2") (pinfunction "2_2") (pintype "passive"))
      (node (ref "Ct2") (pin "2") (pinfunction "2_2") (pintype "passive"))
      (node (ref "R10") (pin "1") (pinfunction "1_1") (pintype "passive"))
      (node (ref "R4") (pin "1") (pinfunction "1_1") (pintype "passive"))
      (node (ref "X") (pin "1") (pinfunction "GND_1") (pintype "passive"))
      (node (ref "X") (pin "10") (pinfunction "AI1-_10") (pintype "passive"))
      (node (ref "X") (pin "20") (pinfunction "GND_20") (pintype "passive"))
      (node (ref "X") (pin "21") (pinfunction "GND_21") (pintype "passive"))
      (node (ref "X") (pin "40") (pinfunction "GND_40") (pintype "passive"))
      (node (ref "X") (pin "8") (pinfunction "AI0-_8") (pintype "passive"))
    )
    (net (code "102") (name "Net-(J-Pad0)") (class "Default")
      (node (ref "J") (pin "0") (pinfunction "0_0") (pintype "passive"))
      (node (ref "R1") (pin "2") (pinfunction "2_2") (pintype "passive"))
    )
    (net (code "103") (name "unconnected-(*-Pad6)") (class "Default")
      (node (ref "*") (pin "6") (pinfunction "6_6") (pintype "passive"))
    )
    (net (code "104") (name "unconnected-(*-Pad7)") (class "Default")
      (node (ref "*") (pin "7") (pinfunction "7_7") (pintype "passive"))
    )
    (net (code "105") (name "unconnected-(10M02A-IO-Pad14)") (class "Default")
      (node (ref "10M02") (pin "14") (pinfunction "IO_14") (pintype "bidirectional"))
    )
    (net (code "106") (name "unconnected-(10M02B-IO-Pad113)") (class "Default")
      (node (ref "10M02") (pin "113") (pinfunction "IO_113") (pintype "bidirectional"))
    )
    (net (code "107") (name "unconnected-(10M02B-IO-Pad115)") (class "Default")
      (node (ref "10M02") (pin "115") (pinfunction "IO_115") (pintype "bidirectional"))
    )
    (net (code "108") (name "unconnected-(10M02B-IO-Pad130)") (class "Default")
      (node (ref "10M02") (pin "130") (pinfunction "IO_130") (pintype "bidirectional"))
    )
    (net (code "109") (name "unconnected-(10M02B-IO-Pad134)") (class "Default")
      (node (ref "10M02") (pin "134") (pinfunction "IO_134") (pintype "bidirectional"))
    )
    (net (code "110") (name "unconnected-(L-0DIO_0-PadR_32)") (class "Default")
      (node (ref "L") (pin "R_32") (pinfunction "0DIO_0_R_32") (pintype "passive"))
    )
    (net (code "111") (name "unconnected-(L-1DIO_0-PadR_49)") (class "Default")
      (node (ref "L") (pin "R_49") (pinfunction "1DIO_0_R_49") (pintype "passive"))
    )
    (net (code "112") (name "unconnected-(L-1DIO_1-PadR_47)") (class "Default")
      (node (ref "L") (pin "R_47") (pinfunction "1DIO_1_R_47") (pintype "passive"))
    )
    (net (code "113") (name "unconnected-(L-1DIO_2-PadR_45)") (class "Default")
      (node (ref "L") (pin "R_45") (pinfunction "1DIO_2_R_45") (pintype "passive"))
    )
    (net (code "114") (name "unconnected-(L-1DIO_9-PadR_31)") (class "Default")
      (node (ref "L") (pin "R_31") (pinfunction "1DIO_9_R_31") (pintype "passive"))
    )
    (net (code "115") (name "unconnected-(L-1DIO_10-PadR_29)") (class "Default")
      (node (ref "L") (pin "R_29") (pinfunction "1DIO_10_R_29") (pintype "passive"))
    )
    (net (code "116") (name "unconnected-(L-1DIO_11-PadR_27)") (class "Default")
      (node (ref "L") (pin "R_27") (pinfunction "1DIO_11_R_27") (pintype "passive"))
    )
    (net (code "117") (name "unconnected-(L-1DIO_38-PadR_28)") (class "Default")
      (node (ref "L") (pin "R_28") (pinfunction "1DIO_38_R_28") (pintype "passive"))
    )
    (net (code "118") (name "unconnected-(L-1DIO_39-PadR_30)") (class "Default")
      (node (ref "L") (pin "R_30") (pinfunction "1DIO_39_R_30") (pintype "passive"))
    )
    (net (code "119") (name "unconnected-(L-3DIO0_0-PadR_97)") (class "Default")
      (node (ref "L") (pin "R_97") (pinfunction "3DIO0_0_R_97") (pintype "passive"))
    )
    (net (code "120") (name "unconnected-(L-3DIO0_1-PadR_95)") (class "Default")
      (node (ref "L") (pin "R_95") (pinfunction "3DIO0_1_R_95") (pintype "passive"))
    )
    (net (code "121") (name "unconnected-(L-3DIO0_2-PadR_93)") (class "Default")
      (node (ref "L") (pin "R_93") (pinfunction "3DIO0_2_R_93") (pintype "passive"))
    )
    (net (code "122") (name "unconnected-(L-3DIO0_3-PadR_91)") (class "Default")
      (node (ref "L") (pin "R_91") (pinfunction "3DIO0_3_R_91") (pintype "passive"))
    )
    (net (code "123") (name "unconnected-(L-3DIO0_4-PadR_89)") (class "Default")
      (node (ref "L") (pin "R_89") (pinfunction "3DIO0_4_R_89") (pintype "passive"))
    )
    (net (code "124") (name "unconnected-(L-3DIO0_5-PadR_87)") (class "Default")
      (node (ref "L") (pin "R_87") (pinfunction "3DIO0_5_R_87") (pintype "passive"))
    )
    (net (code "125") (name "unconnected-(L-3DIO0_6-PadR_85)") (class "Default")
      (node (ref "L") (pin "R_85") (pinfunction "3DIO0_6_R_85") (pintype "passive"))
    )
    (net (code "126") (name "unconnected-(L-3DIO0_7-PadR_83)") (class "Default")
      (node (ref "L") (pin "R_83") (pinfunction "3DIO0_7_R_83") (pintype "passive"))
    )
    (net (code "127") (name "unconnected-(L-3DIO1_0-PadR_81)") (class "Default")
      (node (ref "L") (pin "R_81") (pinfunction "3DIO1_0_R_81") (pintype "passive"))
    )
    (net (code "128") (name "unconnected-(L-3DIO1_1-PadR_79)") (class "Default")
      (node (ref "L") (pin "R_79") (pinfunction "3DIO1_1_R_79") (pintype "passive"))
    )
    (net (code "129") (name "unconnected-(L-3DIO1_2-PadR_77)") (class "Default")
      (node (ref "L") (pin "R_77") (pinfunction "3DIO1_2_R_77") (pintype "passive"))
    )
    (net (code "130") (name "unconnected-(L-3DIO1_3-PadR_75)") (class "Default")
      (node (ref "L") (pin "R_75") (pinfunction "3DIO1_3_R_75") (pintype "passive"))
    )
    (net (code "131") (name "unconnected-(L-3DIO1_4-PadR_73)") (class "Default")
      (node (ref "L") (pin "R_73") (pinfunction "3DIO1_4_R_73") (pintype "passive"))
    )
    (net (code "132") (name "unconnected-(L-3DIO1_5-PadR_71)") (class "Default")
      (node (ref "L") (pin "R_71") (pinfunction "3DIO1_5_R_71") (pintype "passive"))
    )
    (net (code "133") (name "unconnected-(L-3DIO1_6-PadR_69)") (class "Default")
      (node (ref "L") (pin "R_69") (pinfunction "3DIO1_6_R_69") (pintype "passive"))
    )
    (net (code "134") (name "unconnected-(L-3DIO1_7-PadR_67)") (class "Default")
      (node (ref "L") (pin "R_67") (pinfunction "3DIO1_7_R_67") (pintype "passive"))
    )
    (net (code "135") (name "unconnected-(L-3DIO2_0-PadR_65)") (class "Default")
      (node (ref "L") (pin "R_65") (pinfunction "3DIO2_0_R_65") (pintype "passive"))
    )
    (net (code "136") (name "unconnected-(L-3DIO2_1-PadR_63)") (class "Default")
      (node (ref "L") (pin "R_63") (pinfunction "3DIO2_1_R_63") (pintype "passive"))
    )
    (net (code "137") (name "unconnected-(L-3DIO2_2-PadR_61)") (class "Default")
      (node (ref "L") (pin "R_61") (pinfunction "3DIO2_2_R_61") (pintype "passive"))
    )
    (net (code "138") (name "unconnected-(L-3DIO2_3-PadR_59)") (class "Default")
      (node (ref "L") (pin "R_59") (pinfunction "3DIO2_3_R_59") (pintype "passive"))
    )
    (net (code "139") (name "unconnected-(L-3DIO2_4-PadR_57)") (class "Default")
      (node (ref "L") (pin "R_57") (pinfunction "3DIO2_4_R_57") (pintype "passive"))
    )
    (net (code "140") (name "unconnected-(L-3DIO2_5-PadR_55)") (class "Default")
      (node (ref "L") (pin "R_55") (pinfunction "3DIO2_5_R_55") (pintype "passive"))
    )
    (net (code "141") (name "unconnected-(L-3DIO2_6-PadR_53)") (class "Default")
      (node (ref "L") (pin "R_53") (pinfunction "3DIO2_6_R_53") (pintype "passive"))
    )
    (net (code "142") (name "unconnected-(L-3DIO2_7-PadR_51)") (class "Default")
      (node (ref "L") (pin "R_51") (pinfunction "3DIO2_7_R_51") (pintype "passive"))
    )
    (net (code "143") (name "unconnected-(L-4DIO0_0-PadR_56)") (class "Default")
      (node (ref "L") (pin "R_56") (pinfunction "4DIO0_0_R_56") (pintype "passive"))
    )
    (net (code "144") (name "unconnected-(L-4DIO0_1-PadR_58)") (class "Default")
      (node (ref "L") (pin "R_58") (pinfunction "4DIO0_1_R_58") (pintype "passive"))
    )
    (net (code "145") (name "unconnected-(L-4DIO0_2-PadR_60)") (class "Default")
      (node (ref "L") (pin "R_60") (pinfunction "4DIO0_2_R_60") (pintype "passive"))
    )
    (net (code "146") (name "unconnected-(L-4DIO0_3-PadR_62)") (class "Default")
      (node (ref "L") (pin "R_62") (pinfunction "4DIO0_3_R_62") (pintype "passive"))
    )
    (net (code "147") (name "unconnected-(L-4DIO0_4-PadR_64)") (class "Default")
      (node (ref "L") (pin "R_64") (pinfunction "4DIO0_4_R_64") (pintype "passive"))
    )
    (net (code "148") (name "unconnected-(L-4DIO0_5-PadR_66)") (class "Default")
      (node (ref "L") (pin "R_66") (pinfunction "4DIO0_5_R_66") (pintype "passive"))
    )
    (net (code "149") (name "unconnected-(L-4DIO0_6-PadR_68)") (class "Default")
      (node (ref "L") (pin "R_68") (pinfunction "4DIO0_6_R_68") (pintype "passive"))
    )
    (net (code "150") (name "unconnected-(L-4DIO0_7-PadR_70)") (class "Default")
      (node (ref "L") (pin "R_70") (pinfunction "4DIO0_7_R_70") (pintype "passive"))
    )
    (net (code "151") (name "unconnected-(L-4DIO1_0-PadR_72)") (class "Default")
      (node (ref "L") (pin "R_72") (pinfunction "4DIO1_0_R_72") (pintype "passive"))
    )
    (net (code "152") (name "unconnected-(L-4DIO1_1-PadR_74)") (class "Default")
      (node (ref "L") (pin "R_74") (pinfunction "4DIO1_1_R_74") (pintype "passive"))
    )
    (net (code "153") (name "unconnected-(L-4DIO1_2-PadR_76)") (class "Default")
      (node (ref "L") (pin "R_76") (pinfunction "4DIO1_2_R_76") (pintype "passive"))
    )
    (net (code "154") (name "unconnected-(L-4DIO1_3-PadR_78)") (class "Default")
      (node (ref "L") (pin "R_78") (pinfunction "4DIO1_3_R_78") (pintype "passive"))
    )
    (net (code "155") (name "unconnected-(L-4DIO1_4-PadR_80)") (class "Default")
      (node (ref "L") (pin "R_80") (pinfunction "4DIO1_4_R_80") (pintype "passive"))
    )
    (net (code "156") (name "unconnected-(L-4DIO1_5-PadR_82)") (class "Default")
      (node (ref "L") (pin "R_82") (pinfunction "4DIO1_5_R_82") (pintype "passive"))
    )
    (net (code "157") (name "unconnected-(L-4DIO1_6-PadR_84)") (class "Default")
      (node (ref "L") (pin "R_84") (pinfunction "4DIO1_6_R_84") (pintype "passive"))
    )
    (net (code "158") (name "unconnected-(L-4DIO1_7-PadR_86)") (class "Default")
      (node (ref "L") (pin "R_86") (pinfunction "4DIO1_7_R_86") (pintype "passive"))
    )
    (net (code "159") (name "unconnected-(L-4DIO2_0-PadR_88)") (class "Default")
      (node (ref "L") (pin "R_88") (pinfunction "4DIO2_0_R_88") (pintype "passive"))
    )
    (net (code "160") (name "unconnected-(L-4DIO2_1-PadR_90)") (class "Default")
      (node (ref "L") (pin "R_90") (pinfunction "4DIO2_1_R_90") (pintype "passive"))
    )
    (net (code "161") (name "unconnected-(L-4DIO2_2-PadR_92)") (class "Default")
      (node (ref "L") (pin "R_92") (pinfunction "4DIO2_2_R_92") (pintype "passive"))
    )
    (net (code "162") (name "unconnected-(L-4DIO2_3-PadR_94)") (class "Default")
      (node (ref "L") (pin "R_94") (pinfunction "4DIO2_3_R_94") (pintype "passive"))
    )
    (net (code "163") (name "unconnected-(L-4DIO2_4-PadR_96)") (class "Default")
      (node (ref "L") (pin "R_96") (pinfunction "4DIO2_4_R_96") (pintype "passive"))
    )
    (net (code "164") (name "unconnected-(L-4DIO2_5-PadR_98)") (class "Default")
      (node (ref "L") (pin "R_98") (pinfunction "4DIO2_5_R_98") (pintype "passive"))
    )
    (net (code "165") (name "unconnected-(L-4DIO2_6-PadR_100)") (class "Default")
      (node (ref "L") (pin "R_100") (pinfunction "4DIO2_6_R_100") (pintype "passive"))
    )
    (net (code "166") (name "unconnected-(L-4DIO2_7-PadR_99)") (class "Default")
      (node (ref "L") (pin "R_99") (pinfunction "4DIO2_7_R_99") (pintype "passive"))
    )
    (net (code "167") (name "unconnected-(L-A0+-PadR_48)") (class "Default")
      (node (ref "L") (pin "R_48") (pinfunction "A0+_R_48") (pintype "passive"))
    )
    (net (code "168") (name "unconnected-(L-A0--PadR_50)") (class "Default")
      (node (ref "L") (pin "R_50") (pinfunction "A0-_R_50") (pintype "passive"))
    )
    (net (code "169") (name "unconnected-(L-A1+-PadR_54)") (class "Default")
      (node (ref "L") (pin "R_54") (pinfunction "A1+_R_54") (pintype "passive"))
    )
    (net (code "170") (name "unconnected-(L-A1--PadR_52)") (class "Default")
      (node (ref "L") (pin "R_52") (pinfunction "A1-_R_52") (pintype "passive"))
    )
    (net (code "171") (name "unconnected-(R-2DIO_20-PadR_42)") (class "Default")
      (node (ref "R") (pin "R_42") (pinfunction "2DIO_20_R_42") (pintype "passive"))
    )
    (net (code "172") (name "unconnected-(R-2DIO_21-PadR_40)") (class "Default")
      (node (ref "R") (pin "R_40") (pinfunction "2DIO_21_R_40") (pintype "passive"))
    )
    (net (code "173") (name "unconnected-(R-3CLK_0-PadR_88)") (class "Default")
      (node (ref "R") (pin "R_88") (pinfunction "3CLK_0_R_88") (pintype "passive"))
    )
    (net (code "174") (name "unconnected-(R-3COUT-PadR_86)") (class "Default")
      (node (ref "R") (pin "R_86") (pinfunction "3COUT_R_86") (pintype "passive"))
    )
    (net (code "175") (name "unconnected-(R-3PFI_1-PadR_82)") (class "Default")
      (node (ref "R") (pin "R_82") (pinfunction "3PFI_1_R_82") (pintype "passive"))
    )
    (net (code "176") (name "unconnected-(R-3PFI_2-PadR_90)") (class "Default")
      (node (ref "R") (pin "R_90") (pinfunction "3PFI_2_R_90") (pintype "passive"))
    )
    (net (code "177") (name "unconnected-(R-3PFI_3-PadR_84)") (class "Default")
      (node (ref "R") (pin "R_84") (pinfunction "3PFI_3_R_84") (pintype "passive"))
    )
    (net (code "178") (name "unconnected-(R-4CLK_0-PadR_98)") (class "Default")
      (node (ref "R") (pin "R_98") (pinfunction "4CLK_0_R_98") (pintype "passive"))
    )
    (net (code "179") (name "unconnected-(R-4COUT-PadR_96)") (class "Default")
      (node (ref "R") (pin "R_96") (pinfunction "4COUT_R_96") (pintype "passive"))
    )
    (net (code "180") (name "unconnected-(R-4PFI_1-PadR_92)") (class "Default")
      (node (ref "R") (pin "R_92") (pinfunction "4PFI_1_R_92") (pintype "passive"))
    )
    (net (code "181") (name "unconnected-(R-4PFI_2-PadR_100)") (class "Default")
      (node (ref "R") (pin "R_100") (pinfunction "4PFI_2_R_100") (pintype "passive"))
    )
    (net (code "182") (name "unconnected-(R-4PFI_3-PadR_94)") (class "Default")
      (node (ref "R") (pin "R_94") (pinfunction "4PFI_3_R_94") (pintype "passive"))
    )
    (net (code "183") (name "unconnected-(R-A2+-PadR_51)") (class "Default")
      (node (ref "R") (pin "R_51") (pinfunction "A2+_R_51") (pintype "passive"))
    )
    (net (code "184") (name "unconnected-(R-A2--PadR_53)") (class "Default")
      (node (ref "R") (pin "R_53") (pinfunction "A2-_R_53") (pintype "passive"))
    )
    (net (code "185") (name "unconnected-(R-A3+-PadR_47)") (class "Default")
      (node (ref "R") (pin "R_47") (pinfunction "A3+_R_47") (pintype "passive"))
    )
    (net (code "186") (name "unconnected-(R-A3--PadR_49)") (class "Default")
      (node (ref "R") (pin "R_49") (pinfunction "A3-_R_49") (pintype "passive"))
    )
    (net (code "187") (name "unconnected-(R-AGND-PadR_63)") (class "Default")
      (node (ref "R") (pin "R_63") (pinfunction "AGND_R_63") (pintype "passive"))
    )
    (net (code "188") (name "unconnected-(R-AGND-PadR_69)") (class "Default")
      (node (ref "R") (pin "R_69") (pinfunction "AGND_R_69") (pintype "passive"))
    )
    (net (code "189") (name "unconnected-(R-AGND-PadR_75)") (class "Default")
      (node (ref "R") (pin "R_75") (pinfunction "AGND_R_75") (pintype "passive"))
    )
    (net (code "190") (name "unconnected-(R-AGND-PadR_81)") (class "Default")
      (node (ref "R") (pin "R_81") (pinfunction "AGND_R_81") (pintype "passive"))
    )
    (net (code "191") (name "unconnected-(R-AGND-PadR_85)") (class "Default")
      (node (ref "R") (pin "R_85") (pinfunction "AGND_R_85") (pintype "passive"))
    )
    (net (code "192") (name "unconnected-(R-AGND-PadR_87)") (class "Default")
      (node (ref "R") (pin "R_87") (pinfunction "AGND_R_87") (pintype "passive"))
    )
    (net (code "193") (name "unconnected-(R-AGND-PadR_89)") (class "Default")
      (node (ref "R") (pin "R_89") (pinfunction "AGND_R_89") (pintype "passive"))
    )
    (net (code "194") (name "unconnected-(R-AGND-PadR_91)") (class "Default")
      (node (ref "R") (pin "R_91") (pinfunction "AGND_R_91") (pintype "passive"))
    )
    (net (code "195") (name "unconnected-(R-AGND-PadR_93)") (class "Default")
      (node (ref "R") (pin "R_93") (pinfunction "AGND_R_93") (pintype "passive"))
    )
    (net (code "196") (name "unconnected-(R-AGND-PadR_95)") (class "Default")
      (node (ref "R") (pin "R_95") (pinfunction "AGND_R_95") (pintype "passive"))
    )
    (net (code "197") (name "unconnected-(R-AGND-PadR_97)") (class "Default")
      (node (ref "R") (pin "R_97") (pinfunction "AGND_R_97") (pintype "passive"))
    )
    (net (code "198") (name "unconnected-(R-AGND-PadR_99)") (class "Default")
      (node (ref "R") (pin "R_99") (pinfunction "AGND_R_99") (pintype "passive"))
    )
    (net (code "199") (name "unconnected-(R-AI4+-PadR_61)") (class "Default")
      (node (ref "R") (pin "R_61") (pinfunction "AI4+_R_61") (pintype "passive"))
    )
    (net (code "200") (name "unconnected-(R-AI4--PadR_59)") (class "Default")
      (node (ref "R") (pin "R_59") (pinfunction "AI4-_R_59") (pintype "passive"))
    )
    (net (code "201") (name "unconnected-(R-AI5+-PadR_67)") (class "Default")
      (node (ref "R") (pin "R_67") (pinfunction "AI5+_R_67") (pintype "passive"))
    )
    (net (code "202") (name "unconnected-(R-AI5--PadR_65)") (class "Default")
      (node (ref "R") (pin "R_65") (pinfunction "AI5-_R_65") (pintype "passive"))
    )
    (net (code "203") (name "unconnected-(R-AI6+-PadR_73)") (class "Default")
      (node (ref "R") (pin "R_73") (pinfunction "AI6+_R_73") (pintype "passive"))
    )
    (net (code "204") (name "unconnected-(R-AI6--PadR_71)") (class "Default")
      (node (ref "R") (pin "R_71") (pinfunction "AI6-_R_71") (pintype "passive"))
    )
    (net (code "205") (name "unconnected-(R-AI7+-PadR_79)") (class "Default")
      (node (ref "R") (pin "R_79") (pinfunction "AI7+_R_79") (pintype "passive"))
    )
    (net (code "206") (name "unconnected-(R-AI7--PadR_77)") (class "Default")
      (node (ref "R") (pin "R_77") (pinfunction "AI7-_R_77") (pintype "passive"))
    )
    (net (code "207") (name "unconnected-(R-AISENSE-PadR_83)") (class "Default")
      (node (ref "R") (pin "R_83") (pinfunction "AISENSE_R_83") (pintype "passive"))
    )
    (net (code "208") (name "unconnected-(R-DGND-PadR_52)") (class "Default")
      (node (ref "R") (pin "R_52") (pinfunction "DGND_R_52") (pintype "passive"))
    )
    (net (code "209") (name "unconnected-(R-DGND-PadR_54)") (class "Default")
      (node (ref "R") (pin "R_54") (pinfunction "DGND_R_54") (pintype "passive"))
    )
    (net (code "210") (name "unconnected-(R-DGND-PadR_56)") (class "Default")
      (node (ref "R") (pin "R_56") (pinfunction "DGND_R_56") (pintype "passive"))
    )
    (net (code "211") (name "unconnected-(R-DGND-PadR_58)") (class "Default")
      (node (ref "R") (pin "R_58") (pinfunction "DGND_R_58") (pintype "passive"))
    )
    (net (code "212") (name "unconnected-(R-DGND-PadR_60)") (class "Default")
      (node (ref "R") (pin "R_60") (pinfunction "DGND_R_60") (pintype "passive"))
    )
    (net (code "213") (name "unconnected-(R-DGND-PadR_62)") (class "Default")
      (node (ref "R") (pin "R_62") (pinfunction "DGND_R_62") (pintype "passive"))
    )
    (net (code "214") (name "unconnected-(R-DGND-PadR_78)") (class "Default")
      (node (ref "R") (pin "R_78") (pinfunction "DGND_R_78") (pintype "passive"))
    )
    (net (code "215") (name "unconnected-(R-DGND-PadR_80)") (class "Default")
      (node (ref "R") (pin "R_80") (pinfunction "DGND_R_80") (pintype "passive"))
    )
    (net (code "216") (name "unconnected-(R-DVCC12-PadR_66)") (class "Default")
      (node (ref "R") (pin "R_66") (pinfunction "DVCC12_R_66") (pintype "passive"))
    )
    (net (code "217") (name "unconnected-(R-DVCC12-PadR_68)") (class "Default")
      (node (ref "R") (pin "R_68") (pinfunction "DVCC12_R_68") (pintype "passive"))
    )
    (net (code "218") (name "unconnected-(R-DVCC13-PadR_70)") (class "Default")
      (node (ref "R") (pin "R_70") (pinfunction "DVCC13_R_70") (pintype "passive"))
    )
    (net (code "219") (name "unconnected-(R-DVCC13-PadR_72)") (class "Default")
      (node (ref "R") (pin "R_72") (pinfunction "DVCC13_R_72") (pintype "passive"))
    )
    (net (code "220") (name "unconnected-(R-NDVCC14-PadR_74)") (class "Default")
      (node (ref "R") (pin "R_74") (pinfunction "NDVCC14_R_74") (pintype "passive"))
    )
    (net (code "221") (name "unconnected-(R-NDVCC14-PadR_76)") (class "Default")
      (node (ref "R") (pin "R_76") (pinfunction "NDVCC14_R_76") (pintype "passive"))
    )
    (net (code "222") (name "unconnected-(R-PadR_55)") (class "Default")
      (node (ref "R") (pin "R_55") (pinfunction "R_55_R_55") (pintype "passive"))
    )
    (net (code "223") (name "unconnected-(R-PadR_57)") (class "Default")
      (node (ref "R") (pin "R_57") (pinfunction "R_57_R_57") (pintype "passive"))
    )
    (net (code "224") (name "unconnected-(R-PadR_64)") (class "Default")
      (node (ref "R") (pin "R_64") (pinfunction "R_64_R_64") (pintype "passive"))
    )
    (net (code "225") (name "unconnected-(X-AI0+-Pad7)") (class "Default")
      (node (ref "X") (pin "7") (pinfunction "AI0+_7") (pintype "passive"))
    )
    (net (code "226") (name "unconnected-(X-AI1+-Pad9)") (class "Default")
      (node (ref "X") (pin "9") (pinfunction "AI1+_9") (pintype "passive"))
    )
    (net (code "227") (name "unconnected-(X-AI2+-Pad11)") (class "Default")
      (node (ref "X") (pin "11") (pinfunction "AI2+_11") (pintype "passive"))
    )
    (net (code "228") (name "unconnected-(X-AI2--Pad12)") (class "Default")
      (node (ref "X") (pin "12") (pinfunction "AI2-_12") (pintype "passive"))
    )
    (net (code "229") (name "unconnected-(X-AI3+-Pad13)") (class "Default")
      (node (ref "X") (pin "13") (pinfunction "AI3+_13") (pintype "passive"))
    )
    (net (code "230") (name "unconnected-(X-AI3--Pad14)") (class "Default")
      (node (ref "X") (pin "14") (pinfunction "AI3-_14") (pintype "passive"))
    )
    (net (code "231") (name "unconnected-(X-AO0-Pad27)") (class "Default")
      (node (ref "X") (pin "27") (pinfunction "AO0_27") (pintype "passive"))
    )
    (net (code "232") (name "unconnected-(X-AO1-Pad28)") (class "Default")
      (node (ref "X") (pin "28") (pinfunction "AO1_28") (pintype "passive"))
    )
    (net (code "233") (name "unconnected-(X-AO2-Pad29)") (class "Default")
      (node (ref "X") (pin "29") (pinfunction "AO2_29") (pintype "passive"))
    )
    (net (code "234") (name "unconnected-(X-AO3-Pad30)") (class "Default")
      (node (ref "X") (pin "30") (pinfunction "AO3_30") (pintype "passive"))
    )
    (net (code "235") (name "unconnected-(X-AO4-Pad31)") (class "Default")
      (node (ref "X") (pin "31") (pinfunction "AO4_31") (pintype "passive"))
    )
    (net (code "236") (name "unconnected-(X-AO5-Pad32)") (class "Default")
      (node (ref "X") (pin "32") (pinfunction "AO5_32") (pintype "passive"))
    )
    (net (code "237") (name "unconnected-(X-AO6-Pad33)") (class "Default")
      (node (ref "X") (pin "33") (pinfunction "AO6_33") (pintype "passive"))
    )
    (net (code "238") (name "unconnected-(X-AO7-Pad34)") (class "Default")
      (node (ref "X") (pin "34") (pinfunction "AO7_34") (pintype "passive"))
    )
    (net (code "239") (name "unconnected-(X-VCC5-Pad26)") (class "Default")
      (node (ref "X") (pin "26") (pinfunction "VCC5_26") (pintype "passive"))
    )
    (net (code "240") (name "unconnected-(X-VCC6--Pad24)") (class "Default")
      (node (ref "X") (pin "24") (pinfunction "VCC6-_24") (pintype "passive"))
    )
    (net (code "241") (name "unconnected-(X-VCC7-Pad2)") (class "Default")
      (node (ref "X") (pin "2") (pinfunction "VCC7_2") (pintype "passive"))
    )
    (net (code "242") (name "unconnected-(X-VCC7-Pad37)") (class "Default")
      (node (ref "X") (pin "37") (pinfunction "VCC7_37") (pintype "passive"))
    )
    (net (code "243") (name "unconnected-(X-VCC8-Pad3)") (class "Default")
      (node (ref "X") (pin "3") (pinfunction "VCC8_3") (pintype "passive"))
    )
    (net (code "244") (name "unconnected-(X-VCC8-Pad38)") (class "Default")
      (node (ref "X") (pin "38") (pinfunction "VCC8_38") (pintype "passive"))
    )
    (net (code "245") (name "unconnected-(X-VCC9--Pad4)") (class "Default")
      (node (ref "X") (pin "4") (pinfunction "VCC9-_4") (pintype "passive"))
    )
    (net (code "246") (name "unconnected-(X-VCC10-Pad5)") (class "Default")
      (node (ref "X") (pin "5") (pinfunction "VCC10_5") (pintype "passive"))
    )
    (net (code "247") (name "unconnected-(X-VCC10-Pad36)") (class "Default")
      (node (ref "X") (pin "36") (pinfunction "VCC10_36") (pintype "passive"))
    )
    (net (code "248") (name "unconnected-(X-VCC11-Pad6)") (class "Default")
      (node (ref "X") (pin "6") (pinfunction "VCC11_6") (pintype "passive"))
    )
    (net (code "249") (name "unconnected-(X-VCC11-Pad35)") (class "Default")
      (node (ref "X") (pin "35") (pinfunction "VCC11_35") (pintype "passive"))
    )
    (net (code "250") (name "unconnected-(X-VCC12--Pad39)") (class "Default")
      (node (ref "X") (pin "39") (pinfunction "VCC12-_39") (pintype "passive"))
    )
  )
)
